# Remote_Controller.net
KiCad netlist of a schematic drawn in EasyEDA
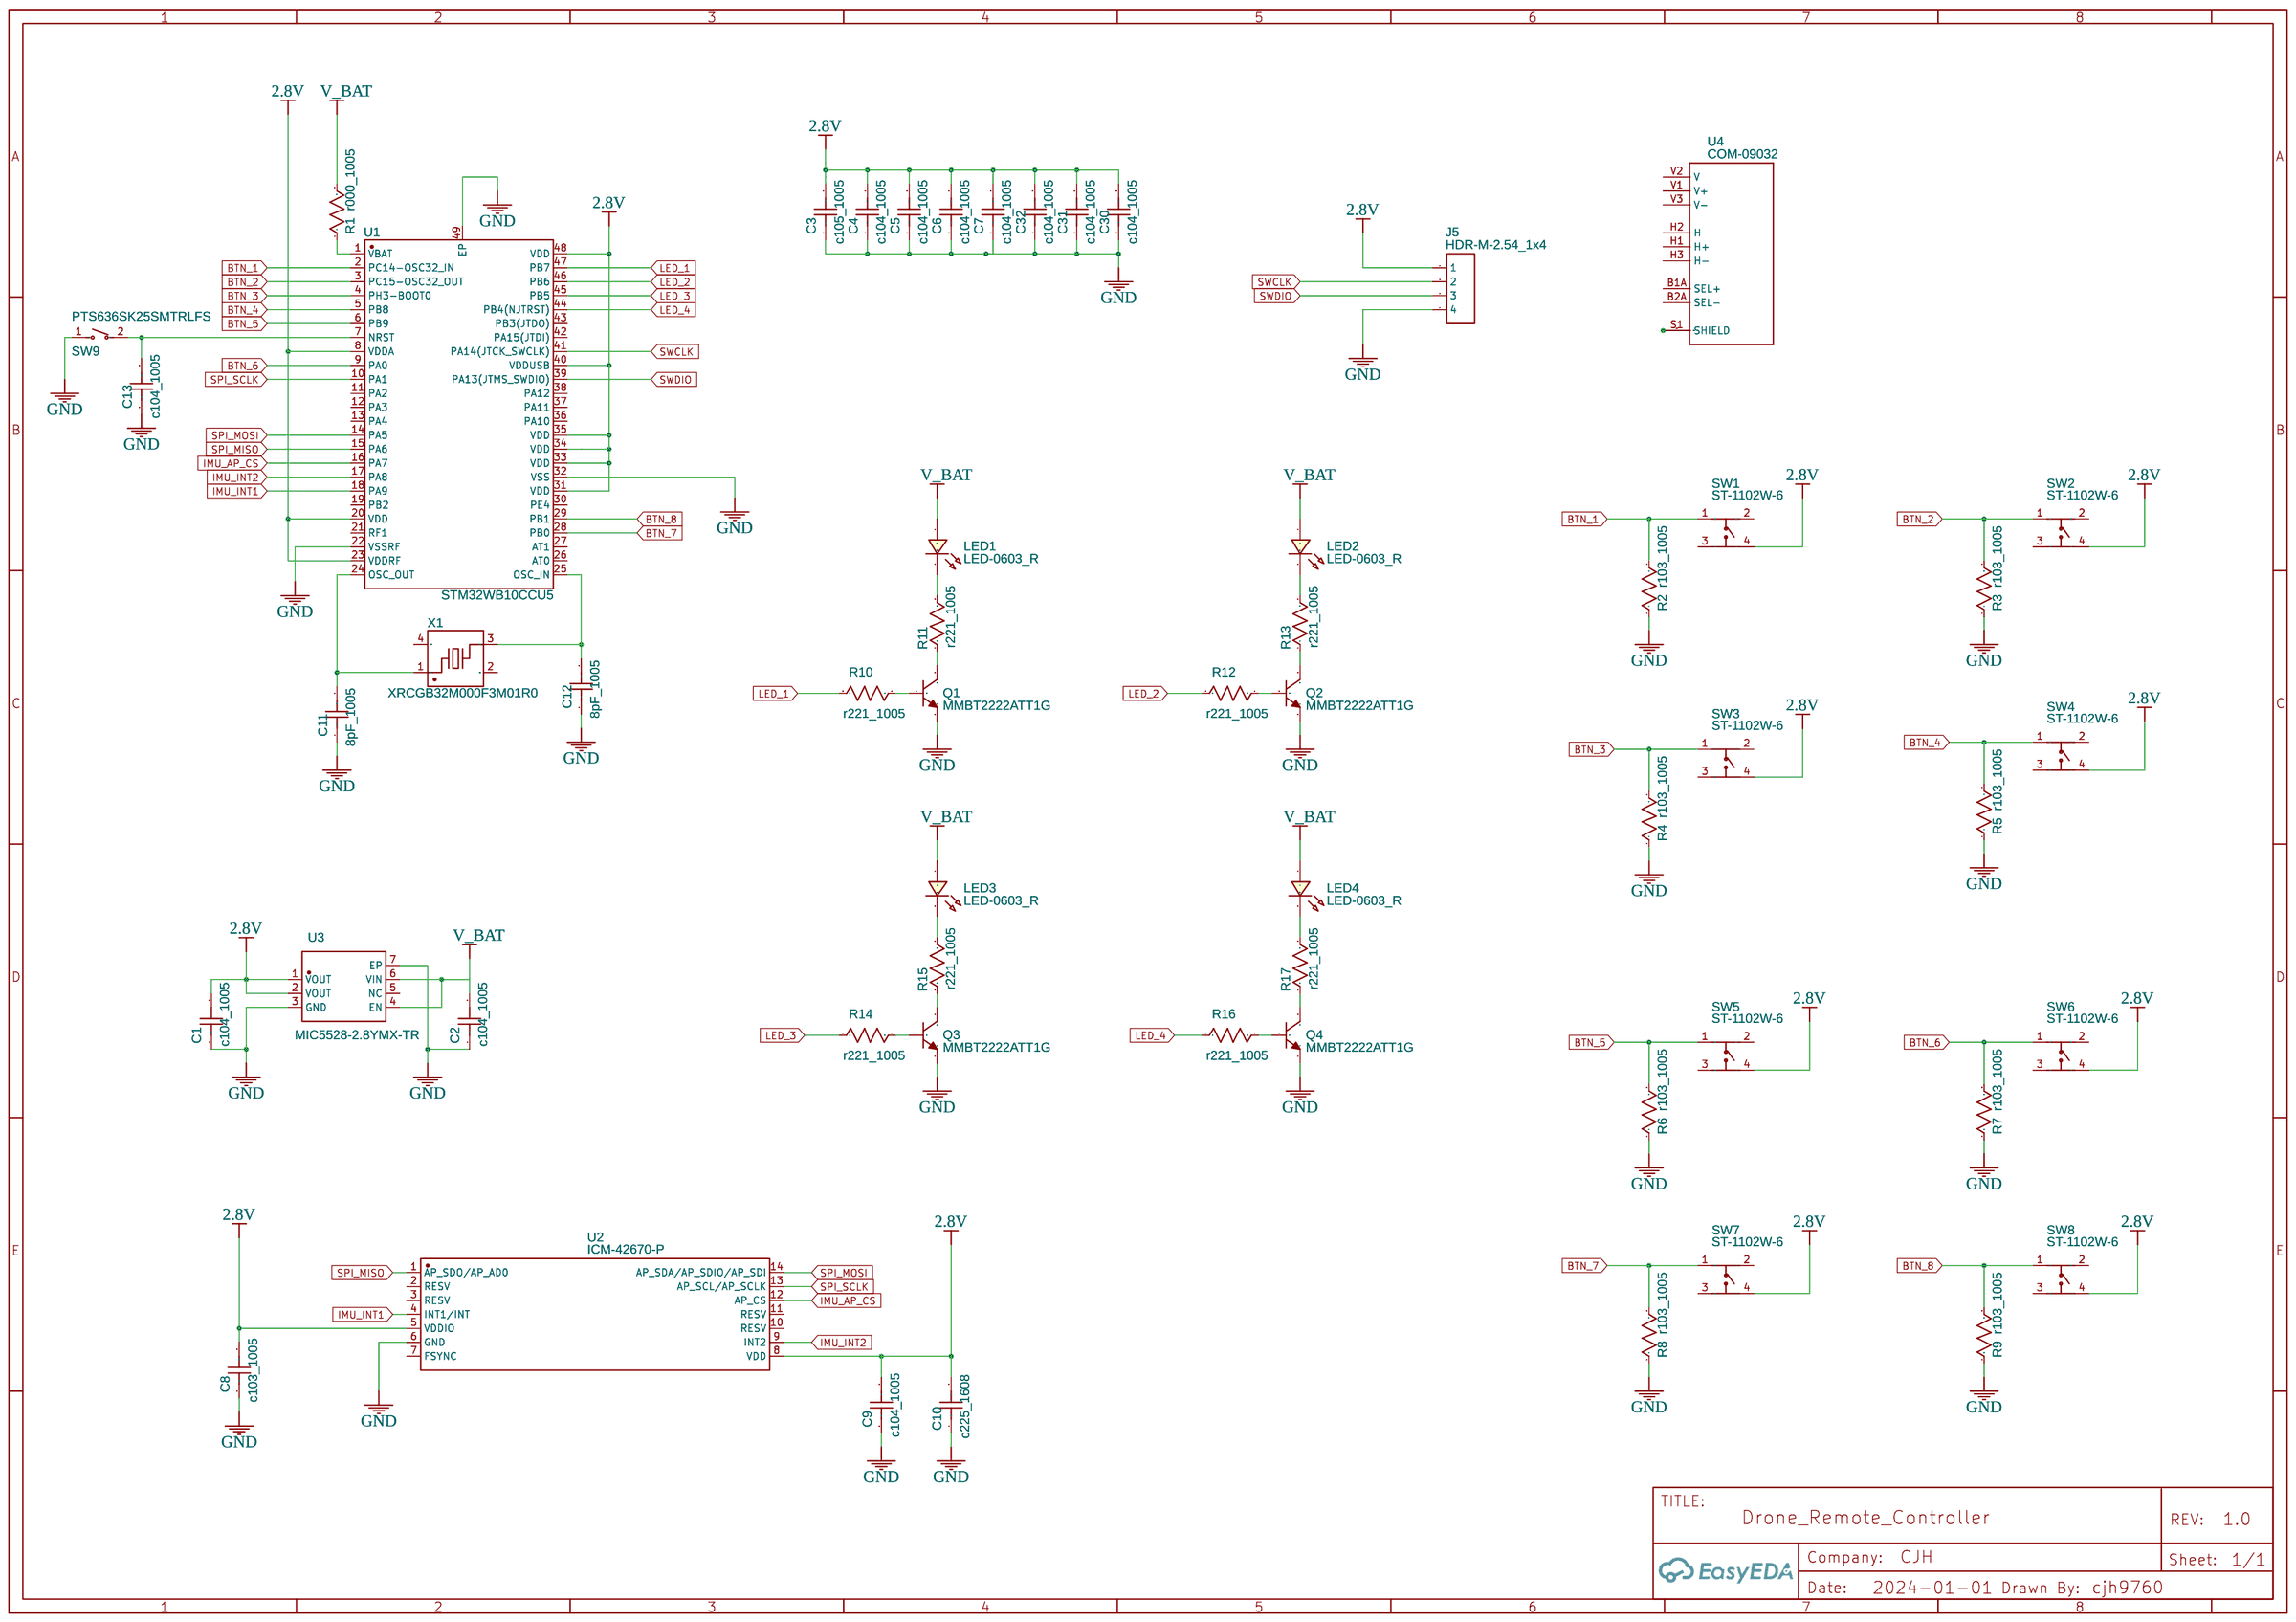
[diagram p0: schematic sheet]

(export (version "E")
  (design (tool "Eeschema 10.0.6"))
  (components
    (comp (ref "C1") (value "c104_1005") (libsource (lib "") (part "C_0402_US")))
    (comp (ref "C2") (value "c104_1005") (libsource (lib "") (part "C_0402_US")))
    (comp (ref "C3") (value "c105_1005") (libsource (lib "") (part "C_0402_US")))
    (comp (ref "C4") (value "c104_1005") (libsource (lib "") (part "C_0402_US")))
    (comp (ref "C5") (value "c104_1005") (libsource (lib "") (part "C_0402_US")))
    (comp (ref "C6") (value "c104_1005") (libsource (lib "") (part "C_0402_US")))
    (comp (ref "C7") (value "c104_1005") (libsource (lib "") (part "C_0402_US")))
    (comp (ref "C8") (value "c103_1005") (libsource (lib "") (part "C_0402_US")))
    (comp (ref "C9") (value "c104_1005") (libsource (lib "") (part "C_0402_US")))
    (comp (ref "C10") (value "c225_1608") (libsource (lib "") (part "C_0603_US")))
    (comp (ref "C11") (value "8pF_1005") (libsource (lib "") (part "C_0402_US")))
    (comp (ref "C12") (value "8pF_1005") (libsource (lib "") (part "C_0402_US")))
    (comp (ref "C13") (value "c104_1005") (libsource (lib "") (part "C_0402_US")))
    (comp (ref "C30") (value "c104_1005") (libsource (lib "") (part "C_0402_US")))
    (comp (ref "C31") (value "c104_1005") (libsource (lib "") (part "C_0402_US")))
    (comp (ref "C32") (value "c104_1005") (libsource (lib "") (part "C_0402_US")))
    (comp (ref "J5") (value "HDR-M-2.54_1x4") (libsource (lib "") (part "HDR-M-2.54_1x4")))
    (comp (ref "LED1")
      (value "LED-0603_R")
      (fields
        (field (name "Manufacturer Part") "19-217/R6C-AL1M2VY/3T")
        (field (name "Manufacturer") "EVERLIGHT(台湾亿光)")
      )
      (libsource (lib "") (part "LED-0603_R"))
    )
    (comp (ref "LED2")
      (value "LED-0603_R")
      (fields
        (field (name "Manufacturer Part") "19-217/R6C-AL1M2VY/3T")
        (field (name "Manufacturer") "EVERLIGHT(台湾亿光)")
      )
      (libsource (lib "") (part "LED-0603_R"))
    )
    (comp (ref "LED3")
      (value "LED-0603_R")
      (fields
        (field (name "Manufacturer Part") "19-217/R6C-AL1M2VY/3T")
        (field (name "Manufacturer") "EVERLIGHT(台湾亿光)")
      )
      (libsource (lib "") (part "LED-0603_R"))
    )
    (comp (ref "LED4")
      (value "LED-0603_R")
      (fields
        (field (name "Manufacturer Part") "19-217/R6C-AL1M2VY/3T")
        (field (name "Manufacturer") "EVERLIGHT(台湾亿光)")
      )
      (libsource (lib "") (part "LED-0603_R"))
    )
    (comp (ref "Q1")
      (value "MMBT2222ATT1G")
      (fields (field (name "Manufacturer") "onsemi(安森美)"))
      (libsource (lib "") (part "MMBT2222ATT1G"))
    )
    (comp (ref "Q2")
      (value "MMBT2222ATT1G")
      (fields (field (name "Manufacturer") "onsemi(安森美)"))
      (libsource (lib "") (part "MMBT2222ATT1G"))
    )
    (comp (ref "Q3")
      (value "MMBT2222ATT1G")
      (fields (field (name "Manufacturer") "onsemi(安森美)"))
      (libsource (lib "") (part "MMBT2222ATT1G"))
    )
    (comp (ref "Q4")
      (value "MMBT2222ATT1G")
      (fields (field (name "Manufacturer") "onsemi(安森美)"))
      (libsource (lib "") (part "MMBT2222ATT1G"))
    )
    (comp (ref "R1") (value "r000_1005") (libsource (lib "") (part "R_0402_US_1")))
    (comp (ref "R2") (value "r103_1005") (libsource (lib "") (part "R_0402_US_1")))
    (comp (ref "R3") (value "r103_1005") (libsource (lib "") (part "R_0402_US_1")))
    (comp (ref "R4") (value "r103_1005") (libsource (lib "") (part "R_0402_US_1")))
    (comp (ref "R5") (value "r103_1005") (libsource (lib "") (part "R_0402_US_1")))
    (comp (ref "R6") (value "r103_1005") (libsource (lib "") (part "R_0402_US_1")))
    (comp (ref "R7") (value "r103_1005") (libsource (lib "") (part "R_0402_US_1")))
    (comp (ref "R8") (value "r103_1005") (libsource (lib "") (part "R_0402_US_1")))
    (comp (ref "R9") (value "r103_1005") (libsource (lib "") (part "R_0402_US_1")))
    (comp (ref "R10") (value "r221_1005") (libsource (lib "") (part "R_0402_US")))
    (comp (ref "R11") (value "r221_1005") (libsource (lib "") (part "R_0402_US_1")))
    (comp (ref "R12") (value "r221_1005") (libsource (lib "") (part "R_0402_US")))
    (comp (ref "R13") (value "r221_1005") (libsource (lib "") (part "R_0402_US_1")))
    (comp (ref "R14") (value "r221_1005") (libsource (lib "") (part "R_0402_US")))
    (comp (ref "R15") (value "r221_1005") (libsource (lib "") (part "R_0402_US_1")))
    (comp (ref "R16") (value "r221_1005") (libsource (lib "") (part "R_0402_US")))
    (comp (ref "R17") (value "r221_1005") (libsource (lib "") (part "R_0402_US_1")))
    (comp (ref "SW1")
      (value "ST-1102W-6")
      (fields (field (name "Manufacturer") "RISHENG(日昇)"))
      (libsource (lib "") (part "ST-1102W-6"))
    )
    (comp (ref "SW2")
      (value "ST-1102W-6")
      (fields (field (name "Manufacturer") "RISHENG(日昇)"))
      (libsource (lib "") (part "ST-1102W-6"))
    )
    (comp (ref "SW3")
      (value "ST-1102W-6")
      (fields (field (name "Manufacturer") "RISHENG(日昇)"))
      (libsource (lib "") (part "ST-1102W-6"))
    )
    (comp (ref "SW4")
      (value "ST-1102W-6")
      (fields (field (name "Manufacturer") "RISHENG(日昇)"))
      (libsource (lib "") (part "ST-1102W-6"))
    )
    (comp (ref "SW5")
      (value "ST-1102W-6")
      (fields (field (name "Manufacturer") "RISHENG(日昇)"))
      (libsource (lib "") (part "ST-1102W-6"))
    )
    (comp (ref "SW6")
      (value "ST-1102W-6")
      (fields (field (name "Manufacturer") "RISHENG(日昇)"))
      (libsource (lib "") (part "ST-1102W-6"))
    )
    (comp (ref "SW7")
      (value "ST-1102W-6")
      (fields (field (name "Manufacturer") "RISHENG(日昇)"))
      (libsource (lib "") (part "ST-1102W-6"))
    )
    (comp (ref "SW8")
      (value "ST-1102W-6")
      (fields (field (name "Manufacturer") "RISHENG(日昇)"))
      (libsource (lib "") (part "ST-1102W-6"))
    )
    (comp (ref "SW9")
      (value "PTS636SK25SMTRLFS")
      (fields (field (name "Manufacturer") "C&K"))
      (libsource (lib "") (part "PTS636SK25SMTRLFS"))
    )
    (comp (ref "U1")
      (value "STM32WB10CCU5")
      (fields (field (name "Manufacturer Part") "STM32WB10CCU UFQFPN48") (field (name "Manufacturer") "ST"))
      (libsource (lib "") (part "STM32WB10CCU5"))
    )
    (comp (ref "U2")
      (value "ICM-42670-P")
      (fields (field (name "Manufacturer") "TDK InvenSense(应美盛)"))
      (libsource (lib "") (part "ICM-42670-P"))
    )
    (comp (ref "U3")
      (value "MIC5528-2.8YMX-TR")
      (fields (field (name "Manufacturer") "MICROCHIP(美国微芯)"))
      (libsource (lib "") (part "MIC5528-2.8YMX-TR"))
    )
    (comp (ref "U4") (value "COM-09032") (libsource (lib "") (part "COM-09032")))
    (comp (ref "X1")
      (value "XRCGB32M000F3M01R0")
      (fields (field (name "Manufacturer Part") "7D016000O01") (field (name "Manufacturer") "HD(浩都频率)"))
      (libsource (lib "") (part "7D016000O01"))
    )
  )
  (nets
    (net (code "1") (name "2.8V") (class "Default")
      (node (ref "C1") (pin "2") (pinfunction "2_2") (pintype "unspecified"))
      (node (ref "C10") (pin "2") (pinfunction "2_2") (pintype "unspecified"))
      (node (ref "C3") (pin "2") (pinfunction "2_2") (pintype "unspecified"))
      (node (ref "C30") (pin "2") (pinfunction "2_2") (pintype "unspecified"))
      (node (ref "C31") (pin "2") (pinfunction "2_2") (pintype "unspecified"))
      (node (ref "C32") (pin "2") (pinfunction "2_2") (pintype "unspecified"))
      (node (ref "C4") (pin "2") (pinfunction "2_2") (pintype "unspecified"))
      (node (ref "C5") (pin "2") (pinfunction "2_2") (pintype "unspecified"))
      (node (ref "C6") (pin "2") (pinfunction "2_2") (pintype "unspecified"))
      (node (ref "C7") (pin "2") (pinfunction "2_2") (pintype "unspecified"))
      (node (ref "C8") (pin "2") (pinfunction "2_2") (pintype "unspecified"))
      (node (ref "C9") (pin "2") (pinfunction "2_2") (pintype "unspecified"))
      (node (ref "J5") (pin "1") (pinfunction "1_1") (pintype "unspecified"))
      (node (ref "SW1") (pin "4") (pinfunction "4_4") (pintype "unspecified"))
      (node (ref "SW2") (pin "4") (pinfunction "4_4") (pintype "unspecified"))
      (node (ref "SW3") (pin "4") (pinfunction "4_4") (pintype "unspecified"))
      (node (ref "SW4") (pin "4") (pinfunction "4_4") (pintype "unspecified"))
      (node (ref "SW5") (pin "4") (pinfunction "4_4") (pintype "unspecified"))
      (node (ref "SW6") (pin "4") (pinfunction "4_4") (pintype "unspecified"))
      (node (ref "SW7") (pin "4") (pinfunction "4_4") (pintype "unspecified"))
      (node (ref "SW8") (pin "4") (pinfunction "4_4") (pintype "unspecified"))
      (node (ref "U1") (pin "20") (pinfunction "VDD_20") (pintype "unspecified"))
      (node (ref "U1") (pin "23") (pinfunction "VDDRF_23") (pintype "unspecified"))
      (node (ref "U1") (pin "31") (pinfunction "VDD_31") (pintype "unspecified"))
      (node (ref "U1") (pin "33") (pinfunction "VDD_33") (pintype "unspecified"))
      (node (ref "U1") (pin "34") (pinfunction "VDD_34") (pintype "unspecified"))
      (node (ref "U1") (pin "35") (pinfunction "VDD_35") (pintype "unspecified"))
      (node (ref "U1") (pin "40") (pinfunction "VDDUSB_40") (pintype "unspecified"))
      (node (ref "U1") (pin "48") (pinfunction "VDD_48") (pintype "unspecified"))
      (node (ref "U1") (pin "8") (pinfunction "VDDA_8") (pintype "unspecified"))
      (node (ref "U2") (pin "5") (pinfunction "VDDIO_5") (pintype "unspecified"))
      (node (ref "U2") (pin "8") (pinfunction "VDD_8") (pintype "unspecified"))
      (node (ref "U3") (pin "1") (pinfunction "VOUT_1") (pintype "unspecified"))
      (node (ref "U3") (pin "2") (pinfunction "VOUT_2") (pintype "unspecified"))
    )
    (net (code "2") (name "BTN_1") (class "Default")
      (node (ref "R2") (pin "2") (pinfunction "2_2") (pintype "unspecified"))
      (node (ref "SW1") (pin "1") (pinfunction "1_1") (pintype "unspecified"))
      (node (ref "U1") (pin "2") (pinfunction "PC14-OSC32_IN_2") (pintype "unspecified"))
    )
    (net (code "3") (name "BTN_2") (class "Default")
      (node (ref "R3") (pin "2") (pinfunction "2_2") (pintype "unspecified"))
      (node (ref "SW2") (pin "1") (pinfunction "1_1") (pintype "unspecified"))
      (node (ref "U1") (pin "3") (pinfunction "PC15-OSC32_OUT_3") (pintype "unspecified"))
    )
    (net (code "4") (name "BTN_3") (class "Default")
      (node (ref "R4") (pin "2") (pinfunction "2_2") (pintype "unspecified"))
      (node (ref "SW3") (pin "1") (pinfunction "1_1") (pintype "unspecified"))
      (node (ref "U1") (pin "4") (pinfunction "PH3-BOOT0_4") (pintype "unspecified"))
    )
    (net (code "5") (name "BTN_4") (class "Default")
      (node (ref "R5") (pin "2") (pinfunction "2_2") (pintype "unspecified"))
      (node (ref "SW4") (pin "1") (pinfunction "1_1") (pintype "unspecified"))
      (node (ref "U1") (pin "5") (pinfunction "PB8_5") (pintype "unspecified"))
    )
    (net (code "6") (name "BTN_5") (class "Default")
      (node (ref "R6") (pin "2") (pinfunction "2_2") (pintype "unspecified"))
      (node (ref "SW5") (pin "1") (pinfunction "1_1") (pintype "unspecified"))
      (node (ref "U1") (pin "6") (pinfunction "PB9_6") (pintype "unspecified"))
    )
    (net (code "7") (name "BTN_6") (class "Default")
      (node (ref "R7") (pin "2") (pinfunction "2_2") (pintype "unspecified"))
      (node (ref "SW6") (pin "1") (pinfunction "1_1") (pintype "unspecified"))
      (node (ref "U1") (pin "9") (pinfunction "PA0_9") (pintype "unspecified"))
    )
    (net (code "8") (name "BTN_7") (class "Default")
      (node (ref "R8") (pin "2") (pinfunction "2_2") (pintype "unspecified"))
      (node (ref "SW7") (pin "1") (pinfunction "1_1") (pintype "unspecified"))
      (node (ref "U1") (pin "28") (pinfunction "PB0_28") (pintype "unspecified"))
    )
    (net (code "9") (name "BTN_8") (class "Default")
      (node (ref "R9") (pin "2") (pinfunction "2_2") (pintype "unspecified"))
      (node (ref "SW8") (pin "1") (pinfunction "1_1") (pintype "unspecified"))
      (node (ref "U1") (pin "29") (pinfunction "PB1_29") (pintype "unspecified"))
    )
    (net (code "10") (name "GND") (class "Default")
      (node (ref "C1") (pin "1") (pinfunction "1_1") (pintype "unspecified"))
      (node (ref "C10") (pin "1") (pinfunction "1_1") (pintype "unspecified"))
      (node (ref "C11") (pin "1") (pinfunction "1_1") (pintype "unspecified"))
      (node (ref "C12") (pin "1") (pinfunction "1_1") (pintype "unspecified"))
      (node (ref "C13") (pin "1") (pinfunction "1_1") (pintype "unspecified"))
      (node (ref "C2") (pin "1") (pinfunction "1_1") (pintype "unspecified"))
      (node (ref "C3") (pin "1") (pinfunction "1_1") (pintype "unspecified"))
      (node (ref "C30") (pin "1") (pinfunction "1_1") (pintype "unspecified"))
      (node (ref "C31") (pin "1") (pinfunction "1_1") (pintype "unspecified"))
      (node (ref "C32") (pin "1") (pinfunction "1_1") (pintype "unspecified"))
      (node (ref "C4") (pin "1") (pinfunction "1_1") (pintype "unspecified"))
      (node (ref "C5") (pin "1") (pinfunction "1_1") (pintype "unspecified"))
      (node (ref "C6") (pin "1") (pinfunction "1_1") (pintype "unspecified"))
      (node (ref "C7") (pin "1") (pinfunction "1_1") (pintype "unspecified"))
      (node (ref "C8") (pin "1") (pinfunction "1_1") (pintype "unspecified"))
      (node (ref "C9") (pin "1") (pinfunction "1_1") (pintype "unspecified"))
      (node (ref "J5") (pin "4") (pinfunction "4_4") (pintype "unspecified"))
      (node (ref "Q1") (pin "2") (pinfunction "E_2") (pintype "unspecified"))
      (node (ref "Q2") (pin "2") (pinfunction "E_2") (pintype "unspecified"))
      (node (ref "Q3") (pin "2") (pinfunction "E_2") (pintype "unspecified"))
      (node (ref "Q4") (pin "2") (pinfunction "E_2") (pintype "unspecified"))
      (node (ref "R2") (pin "1") (pinfunction "1_1") (pintype "unspecified"))
      (node (ref "R3") (pin "1") (pinfunction "1_1") (pintype "unspecified"))
      (node (ref "R4") (pin "1") (pinfunction "1_1") (pintype "unspecified"))
      (node (ref "R5") (pin "1") (pinfunction "1_1") (pintype "unspecified"))
      (node (ref "R6") (pin "1") (pinfunction "1_1") (pintype "unspecified"))
      (node (ref "R7") (pin "1") (pinfunction "1_1") (pintype "unspecified"))
      (node (ref "R8") (pin "1") (pinfunction "1_1") (pintype "unspecified"))
      (node (ref "R9") (pin "1") (pinfunction "1_1") (pintype "unspecified"))
      (node (ref "SW9") (pin "1") (pinfunction "1_1") (pintype "unspecified"))
      (node (ref "U1") (pin "22") (pinfunction "VSSRF_22") (pintype "unspecified"))
      (node (ref "U1") (pin "32") (pinfunction "VSS_32") (pintype "unspecified"))
      (node (ref "U1") (pin "49") (pinfunction "EP_49") (pintype "unspecified"))
      (node (ref "U2") (pin "6") (pinfunction "GND_6") (pintype "unspecified"))
      (node (ref "U3") (pin "3") (pinfunction "GND_3") (pintype "unspecified"))
      (node (ref "U3") (pin "7") (pinfunction "EP_7") (pintype "unspecified"))
    )
    (net (code "11") (name "IMU_AP_CS") (class "Default")
      (node (ref "U1") (pin "16") (pinfunction "PA7_16") (pintype "unspecified"))
      (node (ref "U2") (pin "12") (pinfunction "AP_CS_12") (pintype "unspecified"))
    )
    (net (code "12") (name "IMU_INT1") (class "Default")
      (node (ref "U1") (pin "18") (pinfunction "PA9_18") (pintype "unspecified"))
      (node (ref "U2") (pin "4") (pinfunction "INT1/INT_4") (pintype "unspecified"))
    )
    (net (code "13") (name "IMU_INT2") (class "Default")
      (node (ref "U1") (pin "17") (pinfunction "PA8_17") (pintype "unspecified"))
      (node (ref "U2") (pin "9") (pinfunction "INT2_9") (pintype "unspecified"))
    )
    (net (code "14") (name "LED_1") (class "Default")
      (node (ref "R10") (pin "2") (pinfunction "2_2") (pintype "unspecified"))
      (node (ref "U1") (pin "47") (pinfunction "PB7_47") (pintype "unspecified"))
    )
    (net (code "15") (name "LED_2") (class "Default")
      (node (ref "R12") (pin "2") (pinfunction "2_2") (pintype "unspecified"))
      (node (ref "U1") (pin "46") (pinfunction "PB6_46") (pintype "unspecified"))
    )
    (net (code "16") (name "LED_3") (class "Default")
      (node (ref "R14") (pin "2") (pinfunction "2_2") (pintype "unspecified"))
      (node (ref "U1") (pin "45") (pinfunction "PB5_45") (pintype "unspecified"))
    )
    (net (code "17") (name "LED_4") (class "Default")
      (node (ref "R16") (pin "2") (pinfunction "2_2") (pintype "unspecified"))
      (node (ref "U1") (pin "44") (pinfunction "PB4(NJTRST)_44") (pintype "unspecified"))
    )
    (net (code "18") (name "Net-(LED1-Pad2)") (class "Default")
      (node (ref "LED1") (pin "2") (pinfunction "2_2") (pintype "unspecified"))
      (node (ref "R11") (pin "2") (pinfunction "2_2") (pintype "unspecified"))
    )
    (net (code "19") (name "Net-(LED2-Pad2)") (class "Default")
      (node (ref "LED2") (pin "2") (pinfunction "2_2") (pintype "unspecified"))
      (node (ref "R13") (pin "2") (pinfunction "2_2") (pintype "unspecified"))
    )
    (net (code "20") (name "Net-(LED3-Pad2)") (class "Default")
      (node (ref "LED3") (pin "2") (pinfunction "2_2") (pintype "unspecified"))
      (node (ref "R15") (pin "2") (pinfunction "2_2") (pintype "unspecified"))
    )
    (net (code "21") (name "Net-(LED4-Pad2)") (class "Default")
      (node (ref "LED4") (pin "2") (pinfunction "2_2") (pintype "unspecified"))
      (node (ref "R17") (pin "2") (pinfunction "2_2") (pintype "unspecified"))
    )
    (net (code "22") (name "Net-(Q1-B)") (class "Default")
      (node (ref "Q1") (pin "1") (pinfunction "B_1") (pintype "unspecified"))
      (node (ref "R10") (pin "1") (pinfunction "1_1") (pintype "unspecified"))
    )
    (net (code "23") (name "Net-(Q1-C)") (class "Default")
      (node (ref "Q1") (pin "3") (pinfunction "C_3") (pintype "unspecified"))
      (node (ref "R11") (pin "1") (pinfunction "1_1") (pintype "unspecified"))
    )
    (net (code "24") (name "Net-(Q2-B)") (class "Default")
      (node (ref "Q2") (pin "1") (pinfunction "B_1") (pintype "unspecified"))
      (node (ref "R12") (pin "1") (pinfunction "1_1") (pintype "unspecified"))
    )
    (net (code "25") (name "Net-(Q2-C)") (class "Default")
      (node (ref "Q2") (pin "3") (pinfunction "C_3") (pintype "unspecified"))
      (node (ref "R13") (pin "1") (pinfunction "1_1") (pintype "unspecified"))
    )
    (net (code "26") (name "Net-(Q3-B)") (class "Default")
      (node (ref "Q3") (pin "1") (pinfunction "B_1") (pintype "unspecified"))
      (node (ref "R14") (pin "1") (pinfunction "1_1") (pintype "unspecified"))
    )
    (net (code "27") (name "Net-(Q3-C)") (class "Default")
      (node (ref "Q3") (pin "3") (pinfunction "C_3") (pintype "unspecified"))
      (node (ref "R15") (pin "1") (pinfunction "1_1") (pintype "unspecified"))
    )
    (net (code "28") (name "Net-(Q4-B)") (class "Default")
      (node (ref "Q4") (pin "1") (pinfunction "B_1") (pintype "unspecified"))
      (node (ref "R16") (pin "1") (pinfunction "1_1") (pintype "unspecified"))
    )
    (net (code "29") (name "Net-(Q4-C)") (class "Default")
      (node (ref "Q4") (pin "3") (pinfunction "C_3") (pintype "unspecified"))
      (node (ref "R17") (pin "1") (pinfunction "1_1") (pintype "unspecified"))
    )
    (net (code "30") (name "Net-(U1-NRST)") (class "Default")
      (node (ref "C13") (pin "2") (pinfunction "2_2") (pintype "unspecified"))
      (node (ref "SW9") (pin "2") (pinfunction "2_2") (pintype "unspecified"))
      (node (ref "U1") (pin "7") (pinfunction "NRST_7") (pintype "unspecified"))
    )
    (net (code "31") (name "Net-(U1-OSC_IN)") (class "Default")
      (node (ref "C12") (pin "2") (pinfunction "2_2") (pintype "unspecified"))
      (node (ref "U1") (pin "25") (pinfunction "OSC_IN_25") (pintype "unspecified"))
      (node (ref "X1") (pin "3") (pinfunction "OUT_3") (pintype "input"))
    )
    (net (code "32") (name "Net-(U1-OSC_OUT)") (class "Default")
      (node (ref "C11") (pin "2") (pinfunction "2_2") (pintype "unspecified"))
      (node (ref "U1") (pin "24") (pinfunction "OSC_OUT_24") (pintype "unspecified"))
      (node (ref "X1") (pin "1") (pinfunction "IN_1") (pintype "input"))
    )
    (net (code "33") (name "Net-(U1-VBAT)") (class "Default")
      (node (ref "R1") (pin "1") (pinfunction "1_1") (pintype "unspecified"))
      (node (ref "U1") (pin "1") (pinfunction "VBAT_1") (pintype "unspecified"))
    )
    (net (code "34") (name "Net-(U4-SHIELD-PadS1)") (class "Default")
      (node (ref "U4") (pin "S1") (pinfunction "SHIELD_S1") (pintype "bidirectional"))
      (node (ref "U4") (pin "S2") (pinfunction "SHIELD_S2") (pintype "bidirectional"))
      (node (ref "U4") (pin "S3") (pinfunction "SHIELD_S3") (pintype "bidirectional"))
      (node (ref "U4") (pin "S4") (pinfunction "SHIELD_S4") (pintype "bidirectional"))
    )
    (net (code "35") (name "SPI_MISO") (class "Default")
      (node (ref "U1") (pin "15") (pinfunction "PA6_15") (pintype "unspecified"))
      (node (ref "U2") (pin "1") (pinfunction "AP_SDO/AP_AD0_1") (pintype "unspecified"))
    )
    (net (code "36") (name "SPI_MOSI") (class "Default")
      (node (ref "U1") (pin "14") (pinfunction "PA5_14") (pintype "unspecified"))
      (node (ref "U2") (pin "14") (pinfunction "AP_SDA/AP_SDIO/AP_SDI_14") (pintype "unspecified"))
    )
    (net (code "37") (name "SPI_SCLK") (class "Default")
      (node (ref "U1") (pin "10") (pinfunction "PA1_10") (pintype "unspecified"))
      (node (ref "U2") (pin "13") (pinfunction "AP_SCL/AP_SCLK_13") (pintype "unspecified"))
    )
    (net (code "38") (name "SWCLK") (class "Default")
      (node (ref "J5") (pin "2") (pinfunction "2_2") (pintype "unspecified"))
      (node (ref "U1") (pin "41") (pinfunction "PA14(JTCK_SWCLK)_41") (pintype "unspecified"))
    )
    (net (code "39") (name "SWDIO") (class "Default")
      (node (ref "J5") (pin "3") (pinfunction "3_3") (pintype "unspecified"))
      (node (ref "U1") (pin "39") (pinfunction "PA13(JTMS_SWDIO)_39") (pintype "unspecified"))
    )
    (net (code "40") (name "V_BAT") (class "Default")
      (node (ref "C2") (pin "2") (pinfunction "2_2") (pintype "unspecified"))
      (node (ref "LED1") (pin "1") (pinfunction "1_1") (pintype "unspecified"))
      (node (ref "LED2") (pin "1") (pinfunction "1_1") (pintype "unspecified"))
      (node (ref "LED3") (pin "1") (pinfunction "1_1") (pintype "unspecified"))
      (node (ref "LED4") (pin "1") (pinfunction "1_1") (pintype "unspecified"))
      (node (ref "R1") (pin "2") (pinfunction "2_2") (pintype "unspecified"))
      (node (ref "U3") (pin "4") (pinfunction "EN_4") (pintype "unspecified"))
      (node (ref "U3") (pin "6") (pinfunction "VIN_6") (pintype "unspecified"))
    )
    (net (code "41") (name "unconnected-(SW1-Pad2)") (class "Default")
      (node (ref "SW1") (pin "2") (pinfunction "2_2") (pintype "unspecified"))
    )
    (net (code "42") (name "unconnected-(SW1-Pad3)") (class "Default")
      (node (ref "SW1") (pin "3") (pinfunction "3_3") (pintype "unspecified"))
    )
    (net (code "43") (name "unconnected-(SW2-Pad2)") (class "Default")
      (node (ref "SW2") (pin "2") (pinfunction "2_2") (pintype "unspecified"))
    )
    (net (code "44") (name "unconnected-(SW2-Pad3)") (class "Default")
      (node (ref "SW2") (pin "3") (pinfunction "3_3") (pintype "unspecified"))
    )
    (net (code "45") (name "unconnected-(SW3-Pad2)") (class "Default")
      (node (ref "SW3") (pin "2") (pinfunction "2_2") (pintype "unspecified"))
    )
    (net (code "46") (name "unconnected-(SW3-Pad3)") (class "Default")
      (node (ref "SW3") (pin "3") (pinfunction "3_3") (pintype "unspecified"))
    )
    (net (code "47") (name "unconnected-(SW4-Pad2)") (class "Default")
      (node (ref "SW4") (pin "2") (pinfunction "2_2") (pintype "unspecified"))
    )
    (net (code "48") (name "unconnected-(SW4-Pad3)") (class "Default")
      (node (ref "SW4") (pin "3") (pinfunction "3_3") (pintype "unspecified"))
    )
    (net (code "49") (name "unconnected-(SW5-Pad2)") (class "Default")
      (node (ref "SW5") (pin "2") (pinfunction "2_2") (pintype "unspecified"))
    )
    (net (code "50") (name "unconnected-(SW5-Pad3)") (class "Default")
      (node (ref "SW5") (pin "3") (pinfunction "3_3") (pintype "unspecified"))
    )
    (net (code "51") (name "unconnected-(SW6-Pad2)") (class "Default")
      (node (ref "SW6") (pin "2") (pinfunction "2_2") (pintype "unspecified"))
    )
    (net (code "52") (name "unconnected-(SW6-Pad3)") (class "Default")
      (node (ref "SW6") (pin "3") (pinfunction "3_3") (pintype "unspecified"))
    )
    (net (code "53") (name "unconnected-(SW7-Pad2)") (class "Default")
      (node (ref "SW7") (pin "2") (pinfunction "2_2") (pintype "unspecified"))
    )
    (net (code "54") (name "unconnected-(SW7-Pad3)") (class "Default")
      (node (ref "SW7") (pin "3") (pinfunction "3_3") (pintype "unspecified"))
    )
    (net (code "55") (name "unconnected-(SW8-Pad2)") (class "Default")
      (node (ref "SW8") (pin "2") (pinfunction "2_2") (pintype "unspecified"))
    )
    (net (code "56") (name "unconnected-(SW8-Pad3)") (class "Default")
      (node (ref "SW8") (pin "3") (pinfunction "3_3") (pintype "unspecified"))
    )
    (net (code "57") (name "unconnected-(U1-AT0-Pad26)") (class "Default")
      (node (ref "U1") (pin "26") (pinfunction "AT0_26") (pintype "unspecified"))
    )
    (net (code "58") (name "unconnected-(U1-AT1-Pad27)") (class "Default")
      (node (ref "U1") (pin "27") (pinfunction "AT1_27") (pintype "unspecified"))
    )
    (net (code "59") (name "unconnected-(U1-PA2-Pad11)") (class "Default")
      (node (ref "U1") (pin "11") (pinfunction "PA2_11") (pintype "unspecified"))
    )
    (net (code "60") (name "unconnected-(U1-PA3-Pad12)") (class "Default")
      (node (ref "U1") (pin "12") (pinfunction "PA3_12") (pintype "unspecified"))
    )
    (net (code "61") (name "unconnected-(U1-PA4-Pad13)") (class "Default")
      (node (ref "U1") (pin "13") (pinfunction "PA4_13") (pintype "unspecified"))
    )
    (net (code "62") (name "unconnected-(U1-PA10-Pad36)") (class "Default")
      (node (ref "U1") (pin "36") (pinfunction "PA10_36") (pintype "unspecified"))
    )
    (net (code "63") (name "unconnected-(U1-PA11-Pad37)") (class "Default")
      (node (ref "U1") (pin "37") (pinfunction "PA11_37") (pintype "unspecified"))
    )
    (net (code "64") (name "unconnected-(U1-PA12-Pad38)") (class "Default")
      (node (ref "U1") (pin "38") (pinfunction "PA12_38") (pintype "unspecified"))
    )
    (net (code "65") (name "unconnected-(U1-PA15(JTDI)-Pad42)") (class "Default")
      (node (ref "U1") (pin "42") (pinfunction "PA15(JTDI)_42") (pintype "unspecified"))
    )
    (net (code "66") (name "unconnected-(U1-PB2-Pad19)") (class "Default")
      (node (ref "U1") (pin "19") (pinfunction "PB2_19") (pintype "unspecified"))
    )
    (net (code "67") (name "unconnected-(U1-PB3(JTDO)-Pad43)") (class "Default")
      (node (ref "U1") (pin "43") (pinfunction "PB3(JTDO)_43") (pintype "unspecified"))
    )
    (net (code "68") (name "unconnected-(U1-PE4-Pad30)") (class "Default")
      (node (ref "U1") (pin "30") (pinfunction "PE4_30") (pintype "unspecified"))
    )
    (net (code "69") (name "unconnected-(U1-RF1-Pad21)") (class "Default")
      (node (ref "U1") (pin "21") (pinfunction "RF1_21") (pintype "unspecified"))
    )
    (net (code "70") (name "unconnected-(U2-FSYNC-Pad7)") (class "Default")
      (node (ref "U2") (pin "7") (pinfunction "FSYNC_7") (pintype "unspecified"))
    )
    (net (code "71") (name "unconnected-(U2-RESV-Pad2)") (class "Default")
      (node (ref "U2") (pin "2") (pinfunction "RESV_2") (pintype "unspecified"))
    )
    (net (code "72") (name "unconnected-(U2-RESV-Pad3)") (class "Default")
      (node (ref "U2") (pin "3") (pinfunction "RESV_3") (pintype "unspecified"))
    )
    (net (code "73") (name "unconnected-(U2-RESV-Pad10)") (class "Default")
      (node (ref "U2") (pin "10") (pinfunction "RESV_10") (pintype "unspecified"))
    )
    (net (code "74") (name "unconnected-(U2-RESV-Pad11)") (class "Default")
      (node (ref "U2") (pin "11") (pinfunction "RESV_11") (pintype "unspecified"))
    )
    (net (code "75") (name "unconnected-(U3-NC-Pad5)") (class "Default")
      (node (ref "U3") (pin "5") (pinfunction "NC_5") (pintype "unspecified"))
    )
    (net (code "76") (name "unconnected-(U4-H+-PadH1)") (class "Default")
      (node (ref "U4") (pin "H1") (pinfunction "H+_H1") (pintype "bidirectional"))
    )
    (net (code "77") (name "unconnected-(U4-H--PadH3)") (class "Default")
      (node (ref "U4") (pin "H3") (pinfunction "H-_H3") (pintype "bidirectional"))
    )
    (net (code "78") (name "unconnected-(U4-H-PadH2)") (class "Default")
      (node (ref "U4") (pin "H2") (pinfunction "H_H2") (pintype "bidirectional"))
    )
    (net (code "79") (name "unconnected-(U4-SEL+-PadB1A)") (class "Default")
      (node (ref "U4") (pin "B1A") (pinfunction "SEL+_B1A") (pintype "bidirectional"))
    )
    (net (code "80") (name "unconnected-(U4-SEL--PadB2A)") (class "Default")
      (node (ref "U4") (pin "B2A") (pinfunction "SEL-_B2A") (pintype "bidirectional"))
    )
    (net (code "81") (name "unconnected-(U4-V+-PadV1)") (class "Default")
      (node (ref "U4") (pin "V1") (pinfunction "V+_V1") (pintype "bidirectional"))
    )
    (net (code "82") (name "unconnected-(U4-V--PadV3)") (class "Default")
      (node (ref "U4") (pin "V3") (pinfunction "V-_V3") (pintype "bidirectional"))
    )
    (net (code "83") (name "unconnected-(U4-V-PadV2)") (class "Default")
      (node (ref "U4") (pin "V2") (pinfunction "V_V2") (pintype "bidirectional"))
    )
    (net (code "84") (name "unconnected-(X1-GND-Pad2)") (class "Default")
      (node (ref "X1") (pin "2") (pinfunction "GND_2") (pintype "input"))
    )
    (net (code "85") (name "unconnected-(X1-GND-Pad4)") (class "Default")
      (node (ref "X1") (pin "4") (pinfunction "GND_4") (pintype "input"))
    )
  )
)
